# V3.net
KiCad netlist of a schematic drawn in Altium Designer
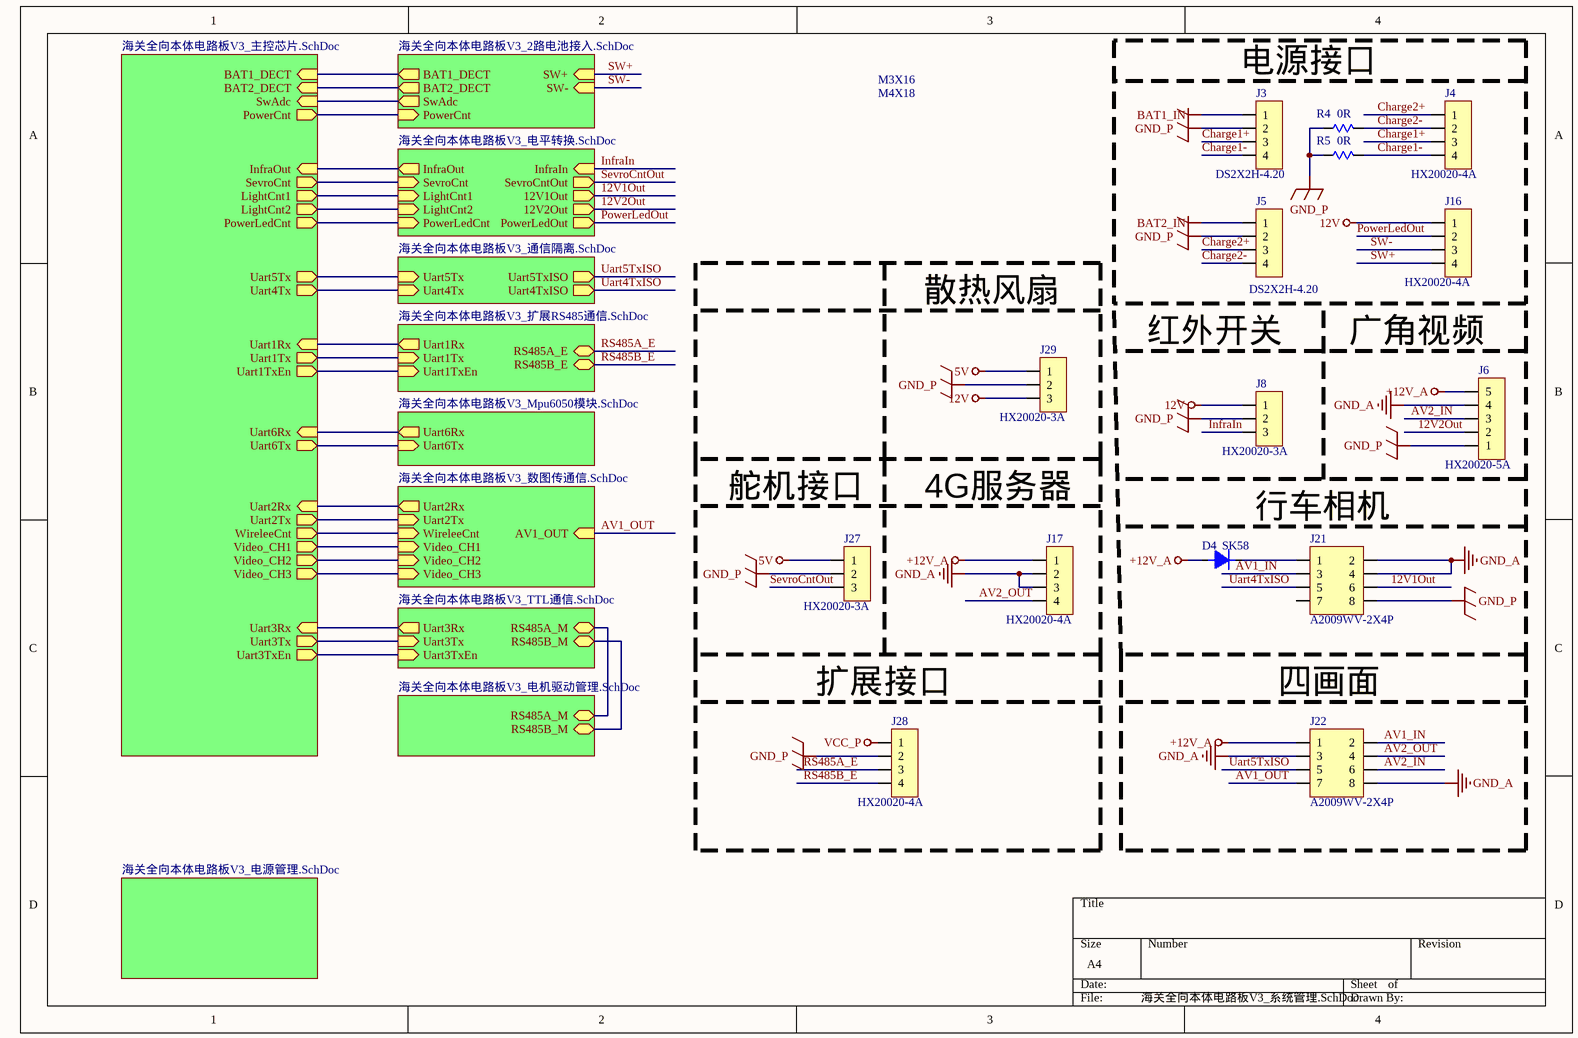
[diagram p0: 海关全向本体电路板V3_系统管理.SchDoc]

(export (version "E")
  (design (tool "Eeschema 10.0.6"))
  (components
    (comp (ref "D4")
      (value "SK58")
      (footprint "SMB")
      (description "Diode")
      (libsource (lib "*") (part "DIODE1"))
    )
    (comp (ref "J3")
      (value "DS2X2H-4.20")
      (footprint "5566-04A")
      (libsource (lib "Connector Class") (part "HEADER1X4"))
    )
    (comp (ref "J4")
      (value "HX20020-4A")
      (footprint "HX20020-4A")
      (libsource (lib "Connector Class") (part "HEADER1X4"))
    )
    (comp (ref "J5")
      (value "DS2X2H-4.20")
      (footprint "5566-04A")
      (libsource (lib "Connector Class") (part "HEADER1X4"))
    )
    (comp (ref "J6")
      (value "HX20020-5A")
      (footprint "HX20020-5A")
      (libsource (lib "Connector Class") (part "HEADER1X5"))
    )
    (comp (ref "J8")
      (value "HX20020-3A")
      (footprint "HX20020-3A")
      (libsource (lib "Connector Class") (part "HEADER1X3"))
    )
    (comp (ref "J16")
      (value "HX20020-4A")
      (footprint "HX20020-4A")
      (libsource (lib "Connector Class") (part "HEADER1X4"))
    )
    (comp (ref "J17")
      (value "HX20020-4A")
      (footprint "HX20020-4A")
      (libsource (lib "Connector Class") (part "HEADER1X4"))
    )
    (comp (ref "J21")
      (value "A2009WV-2X4P")
      (footprint "A2009WV-2X4P")
      (libsource (lib "Connector Class") (part "HEADER2X4"))
    )
    (comp (ref "J22")
      (value "A2009WV-2X4P")
      (footprint "A2009WV-2X4P")
      (libsource (lib "Connector Class") (part "HEADER2X4"))
    )
    (comp (ref "J27")
      (value "HX20020-3A")
      (footprint "HX20020-3A")
      (libsource (lib "Connector Class") (part "HEADER1X3"))
    )
    (comp (ref "J28")
      (value "HX20020-4A")
      (footprint "HX20020-4A")
      (libsource (lib "Connector Class") (part "HEADER1X4"))
    )
    (comp (ref "J29")
      (value "HX20020-3A")
      (footprint "HX20020-3A")
      (libsource (lib "Connector Class") (part "HEADER1X3"))
    )
    (comp (ref "R4")
      (value "0R")
      (footprint "R1206-S")
      (description "Resistor")
      (fields (field (name "PUBLISHER") "Altium Limited"))
      (libsource (lib "Passive Components Class") (part "RES"))
    )
    (comp (ref "R5")
      (value "0R")
      (footprint "R1206-S")
      (description "Resistor")
      (fields (field (name "PUBLISHER") "Altium Limited"))
      (libsource (lib "Passive Components Class") (part "RES"))
    )
  )
  (nets
    (net (code "1") (name "+12V_A") (class "Default")
      (node (ref "D4") (pin "1") (pinfunction "A_1") (pintype "passive"))
      (node (ref "J17") (pin "1") (pinfunction "1_1") (pintype "passive"))
      (node (ref "J22") (pin "1") (pinfunction "1_1") (pintype "passive"))
      (node (ref "J6") (pin "5") (pinfunction "5_5") (pintype "passive"))
    )
    (net (code "2") (name "/12V1Out") (class "Default")
      (node (ref "J21") (pin "6") (pinfunction "6_6") (pintype "passive"))
    )
    (net (code "3") (name "/12V2Out") (class "Default")
      (node (ref "J6") (pin "2") (pinfunction "2_2") (pintype "passive"))
    )
    (net (code "4") (name "/AV1_IN") (class "Default")
      (node (ref "J21") (pin "3") (pinfunction "3_3") (pintype "passive"))
      (node (ref "J22") (pin "2") (pinfunction "2_2") (pintype "passive"))
    )
    (net (code "5") (name "/AV1_OUT") (class "Default")
      (node (ref "J22") (pin "7") (pinfunction "7_7") (pintype "passive"))
    )
    (net (code "6") (name "/AV2_IN") (class "Default")
      (node (ref "J22") (pin "6") (pinfunction "6_6") (pintype "passive"))
      (node (ref "J6") (pin "3") (pinfunction "3_3") (pintype "passive"))
    )
    (net (code "7") (name "/AV2_OUT") (class "Default")
      (node (ref "J17") (pin "4") (pinfunction "4_4") (pintype "passive"))
      (node (ref "J22") (pin "4") (pinfunction "4_4") (pintype "passive"))
    )
    (net (code "10") (name "/Charge1+") (class "Default")
      (node (ref "J3") (pin "3") (pinfunction "3_3") (pintype "passive"))
      (node (ref "J4") (pin "3") (pinfunction "3_3") (pintype "passive"))
    )
    (net (code "11") (name "/Charge1-") (class "Default")
      (node (ref "J3") (pin "4") (pinfunction "4_4") (pintype "passive"))
      (node (ref "J4") (pin "4") (pinfunction "4_4") (pintype "passive"))
      (node (ref "R5") (pin "2") (pinfunction "2_2") (pintype "passive"))
    )
    (net (code "12") (name "/Charge2+") (class "Default")
      (node (ref "J4") (pin "1") (pinfunction "1_1") (pintype "passive"))
      (node (ref "J5") (pin "3") (pinfunction "3_3") (pintype "passive"))
    )
    (net (code "13") (name "/Charge2-") (class "Default")
      (node (ref "J4") (pin "2") (pinfunction "2_2") (pintype "passive"))
      (node (ref "J5") (pin "4") (pinfunction "4_4") (pintype "passive"))
      (node (ref "R4") (pin "2") (pinfunction "2_2") (pintype "passive"))
    )
    (net (code "14") (name "/InfraIn") (class "Default")
      (node (ref "J8") (pin "3") (pinfunction "3_3") (pintype "passive"))
    )
    (net (code "20") (name "/PowerLedOut") (class "Default")
      (node (ref "J16") (pin "2") (pinfunction "2_2") (pintype "passive"))
    )
    (net (code "21") (name "/RS485A_E") (class "Default")
      (node (ref "J28") (pin "3") (pinfunction "3_3") (pintype "passive"))
    )
    (net (code "23") (name "/RS485B_E") (class "Default")
      (node (ref "J28") (pin "4") (pinfunction "4_4") (pintype "passive"))
    )
    (net (code "25") (name "/SW+") (class "Default")
      (node (ref "J16") (pin "4") (pinfunction "4_4") (pintype "passive"))
    )
    (net (code "26") (name "/SW-") (class "Default")
      (node (ref "J16") (pin "3") (pinfunction "3_3") (pintype "passive"))
    )
    (net (code "28") (name "/SevroCntOut") (class "Default")
      (node (ref "J27") (pin "3") (pinfunction "3_3") (pintype "passive"))
    )
    (net (code "39") (name "/Uart4TxISO") (class "Default")
      (node (ref "J21") (pin "5") (pinfunction "5_5") (pintype "passive"))
    )
    (net (code "41") (name "/Uart5TxISO") (class "Default")
      (node (ref "J22") (pin "5") (pinfunction "5_5") (pintype "passive"))
    )
    (net (code "48") (name "5V") (class "Default")
      (node (ref "J27") (pin "1") (pinfunction "1_1") (pintype "passive"))
      (node (ref "J29") (pin "1") (pinfunction "1_1") (pintype "passive"))
    )
    (net (code "49") (name "12V") (class "Default")
      (node (ref "J16") (pin "1") (pinfunction "1_1") (pintype "passive"))
      (node (ref "J29") (pin "3") (pinfunction "3_3") (pintype "passive"))
      (node (ref "J8") (pin "1") (pinfunction "1_1") (pintype "passive"))
    )
    (net (code "50") (name "BAT1_IN") (class "Default")
      (node (ref "J3") (pin "1") (pinfunction "1_1") (pintype "passive"))
    )
    (net (code "51") (name "BAT2_IN") (class "Default")
      (node (ref "J5") (pin "1") (pinfunction "1_1") (pintype "passive"))
    )
    (net (code "52") (name "GND_A") (class "Default")
      (node (ref "J17") (pin "2") (pinfunction "2_2") (pintype "passive"))
      (node (ref "J17") (pin "3") (pinfunction "3_3") (pintype "passive"))
      (node (ref "J21") (pin "2") (pinfunction "2_2") (pintype "passive"))
      (node (ref "J21") (pin "4") (pinfunction "4_4") (pintype "passive"))
      (node (ref "J22") (pin "3") (pinfunction "3_3") (pintype "passive"))
      (node (ref "J22") (pin "8") (pinfunction "8_8") (pintype "passive"))
      (node (ref "J6") (pin "4") (pinfunction "4_4") (pintype "passive"))
    )
    (net (code "53") (name "GND_P") (class "Default")
      (node (ref "J21") (pin "8") (pinfunction "8_8") (pintype "passive"))
      (node (ref "J27") (pin "2") (pinfunction "2_2") (pintype "passive"))
      (node (ref "J28") (pin "2") (pinfunction "2_2") (pintype "passive"))
      (node (ref "J29") (pin "2") (pinfunction "2_2") (pintype "passive"))
      (node (ref "J3") (pin "2") (pinfunction "2_2") (pintype "passive"))
      (node (ref "J5") (pin "2") (pinfunction "2_2") (pintype "passive"))
      (node (ref "J6") (pin "1") (pinfunction "1_1") (pintype "passive"))
      (node (ref "J8") (pin "2") (pinfunction "2_2") (pintype "passive"))
      (node (ref "R4") (pin "1") (pinfunction "1_1") (pintype "passive"))
      (node (ref "R5") (pin "1") (pinfunction "1_1") (pintype "passive"))
    )
    (net (code "54") (name "Net-(D4-K)") (class "Default")
      (node (ref "D4") (pin "2") (pinfunction "K_2") (pintype "passive"))
      (node (ref "J21") (pin "1") (pinfunction "1_1") (pintype "passive"))
    )
    (net (code "55") (name "VCC_P") (class "Default")
      (node (ref "J28") (pin "1") (pinfunction "1_1") (pintype "passive"))
    )
    (net (code "56") (name "unconnected-(J21-Pad7)") (class "Default")
      (node (ref "J21") (pin "7") (pinfunction "7_7") (pintype "passive"))
    )
  )
)
